# untitled.net
KiCad netlist of a schematic drawn in EAGLE
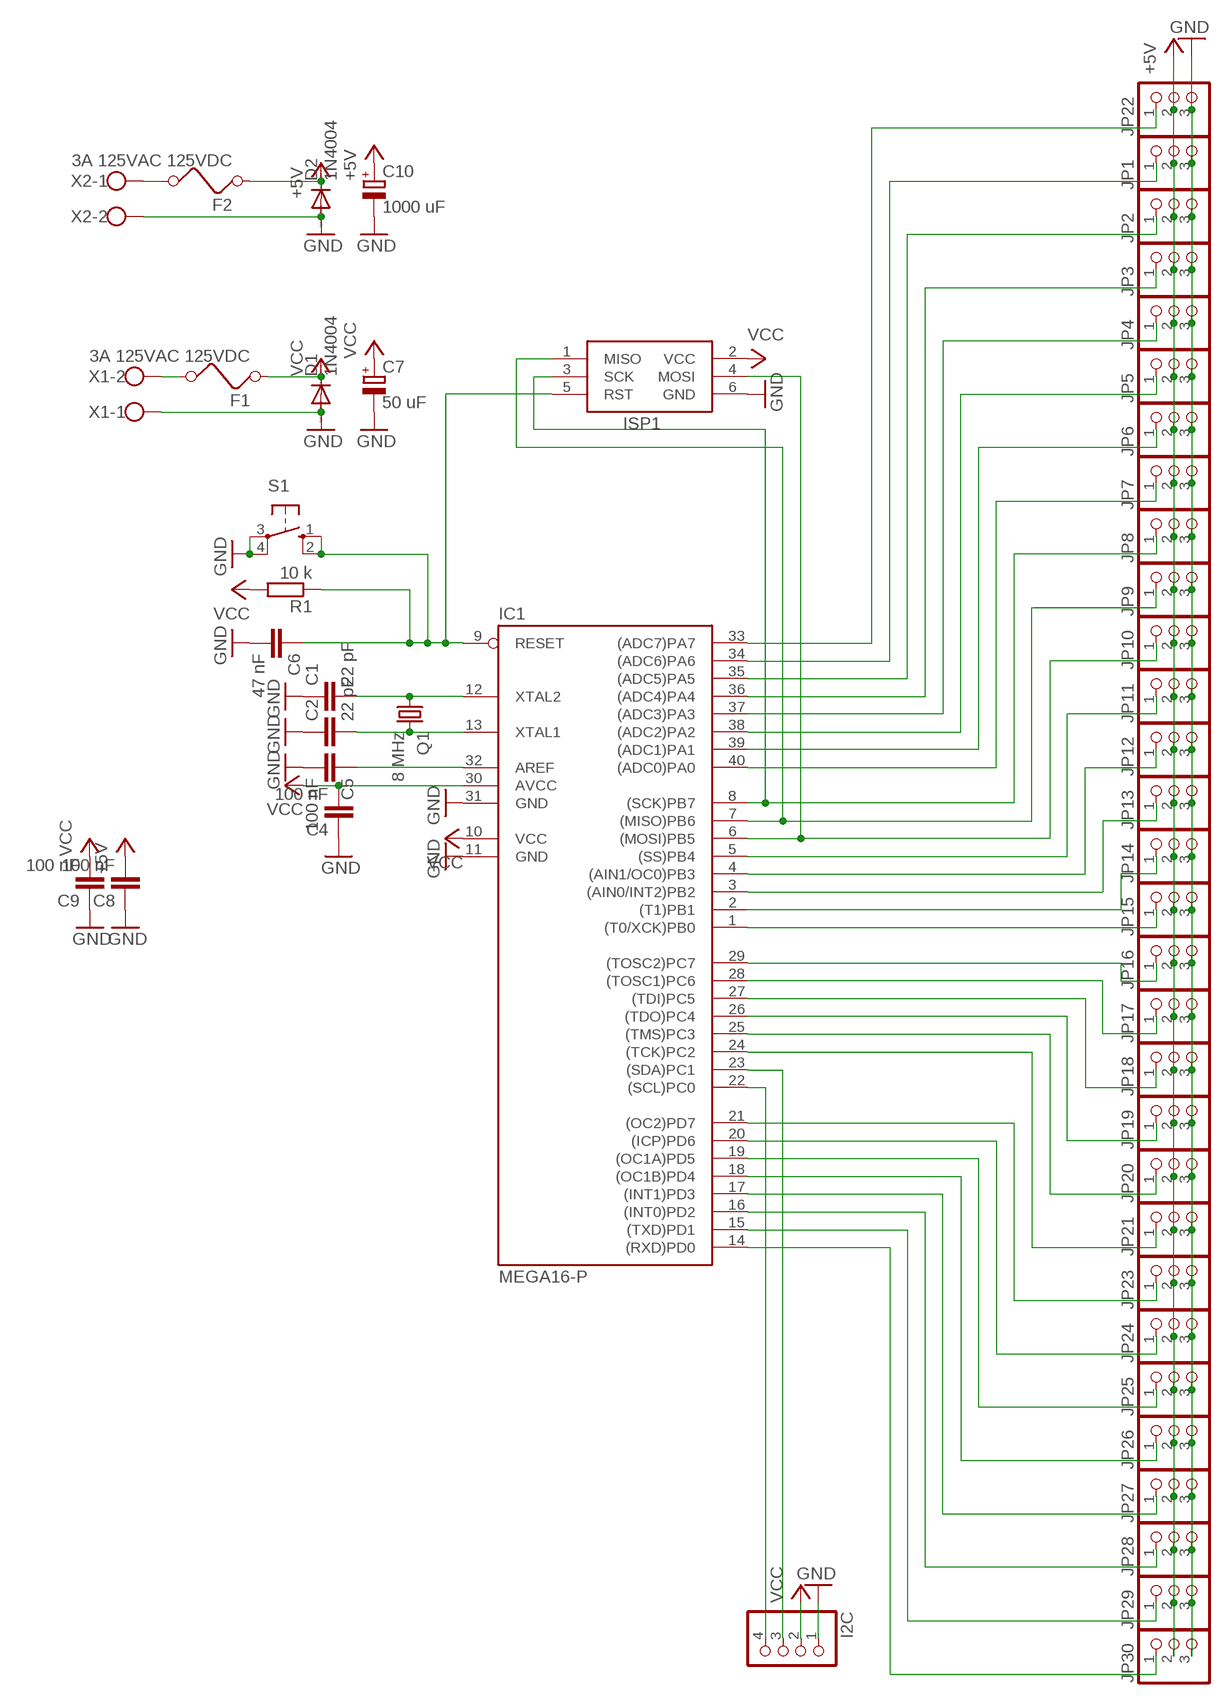
[diagram p0: schematic, sheet 1]

(export (version "E")
  (design (tool "Eeschema 10.0.6"))
  (components
    (comp (ref "C1")
      (value "22 pF")
      (footprint "eagle-import:C0805")
      (libsource (lib "eagle-import") (part "C-EUC0805"))
    )
    (comp (ref "C2")
      (value "22 pF")
      (footprint "eagle-import:C0805")
      (libsource (lib "eagle-import") (part "C-EUC0805"))
    )
    (comp (ref "C4")
      (value "100 nF")
      (footprint "eagle-import:C0805")
      (libsource (lib "eagle-import") (part "C-EUC0805"))
    )
    (comp (ref "C5")
      (value "100 nF")
      (footprint "eagle-import:C0805")
      (libsource (lib "eagle-import") (part "C-EUC0805"))
    )
    (comp (ref "C6")
      (value "47 nF")
      (footprint "eagle-import:C0805")
      (libsource (lib "eagle-import") (part "C-EUC0805"))
    )
    (comp (ref "C7")
      (value "50 uF")
      (footprint "eagle-import:E2-5")
      (libsource (lib "eagle-import") (part "CPOL-EUE2-5"))
    )
    (comp (ref "C8")
      (value "100 nF")
      (footprint "eagle-import:C0805")
      (libsource (lib "eagle-import") (part "C-EUC0805"))
    )
    (comp (ref "C9")
      (value "100 nF")
      (footprint "eagle-import:C0805")
      (libsource (lib "eagle-import") (part "C-EUC0805"))
    )
    (comp (ref "C10")
      (value "1000 uF")
      (footprint "eagle-import:E2-5")
      (libsource (lib "eagle-import") (part "CPOL-EUE2-5"))
    )
    (comp (ref "D1")
      (value "1N4004")
      (footprint "eagle-import:DO214AC")
      (libsource (lib "eagle-import") (part "DIODE-DO214AC"))
    )
    (comp (ref "D2")
      (value "1N4004")
      (footprint "eagle-import:DO214AC")
      (libsource (lib "eagle-import") (part "DIODE-DO214AC"))
    )
    (comp (ref "F1")
      (value "3A 125VAC 125VDC")
      (footprint "eagle-import:FUSE")
      (libsource (lib "eagle-import") (part "FUSE"))
    )
    (comp (ref "F2")
      (value "3A 125VAC 125VDC")
      (footprint "eagle-import:FUSE")
      (libsource (lib "eagle-import") (part "FUSE"))
    )
    (comp (ref "I2C")
      (value "PINHD-1X4")
      (footprint "eagle-import:1X04")
      (libsource (lib "eagle-import") (part "PINHD-1X4"))
    )
    (comp (ref "IC1")
      (value "MEGA16-P")
      (footprint "eagle-import:DIL40")
      (fields (field (name "MPN") "ATMEGA16-16PU"))
      (libsource (lib "eagle-import") (part "MEGA16-P"))
    )
    (comp (ref "ISP1")
      (value "AVRISP-6")
      (footprint "eagle-import:AVRISP")
      (libsource (lib "eagle-import") (part "AVRISP-6"))
    )
    (comp (ref "JP1")
      (value "PINHD-1X3")
      (footprint "eagle-import:1X03")
      (libsource (lib "eagle-import") (part "PINHD-1X3"))
    )
    (comp (ref "JP2")
      (value "PINHD-1X3")
      (footprint "eagle-import:1X03")
      (libsource (lib "eagle-import") (part "PINHD-1X3"))
    )
    (comp (ref "JP3")
      (value "PINHD-1X3")
      (footprint "eagle-import:1X03")
      (libsource (lib "eagle-import") (part "PINHD-1X3"))
    )
    (comp (ref "JP4")
      (value "PINHD-1X3")
      (footprint "eagle-import:1X03")
      (libsource (lib "eagle-import") (part "PINHD-1X3"))
    )
    (comp (ref "JP5")
      (value "PINHD-1X3")
      (footprint "eagle-import:1X03")
      (libsource (lib "eagle-import") (part "PINHD-1X3"))
    )
    (comp (ref "JP6")
      (value "PINHD-1X3")
      (footprint "eagle-import:1X03")
      (libsource (lib "eagle-import") (part "PINHD-1X3"))
    )
    (comp (ref "JP7")
      (value "PINHD-1X3")
      (footprint "eagle-import:1X03")
      (libsource (lib "eagle-import") (part "PINHD-1X3"))
    )
    (comp (ref "JP8")
      (value "PINHD-1X3")
      (footprint "eagle-import:1X03")
      (libsource (lib "eagle-import") (part "PINHD-1X3"))
    )
    (comp (ref "JP9")
      (value "PINHD-1X3")
      (footprint "eagle-import:1X03")
      (libsource (lib "eagle-import") (part "PINHD-1X3"))
    )
    (comp (ref "JP10")
      (value "PINHD-1X3")
      (footprint "eagle-import:1X03")
      (libsource (lib "eagle-import") (part "PINHD-1X3"))
    )
    (comp (ref "JP11")
      (value "PINHD-1X3")
      (footprint "eagle-import:1X03")
      (libsource (lib "eagle-import") (part "PINHD-1X3"))
    )
    (comp (ref "JP12")
      (value "PINHD-1X3")
      (footprint "eagle-import:1X03")
      (libsource (lib "eagle-import") (part "PINHD-1X3"))
    )
    (comp (ref "JP13")
      (value "PINHD-1X3")
      (footprint "eagle-import:1X03")
      (libsource (lib "eagle-import") (part "PINHD-1X3"))
    )
    (comp (ref "JP14")
      (value "PINHD-1X3")
      (footprint "eagle-import:1X03")
      (libsource (lib "eagle-import") (part "PINHD-1X3"))
    )
    (comp (ref "JP15")
      (value "PINHD-1X3")
      (footprint "eagle-import:1X03")
      (libsource (lib "eagle-import") (part "PINHD-1X3"))
    )
    (comp (ref "JP16")
      (value "PINHD-1X3")
      (footprint "eagle-import:1X03")
      (libsource (lib "eagle-import") (part "PINHD-1X3"))
    )
    (comp (ref "JP17")
      (value "PINHD-1X3")
      (footprint "eagle-import:1X03")
      (libsource (lib "eagle-import") (part "PINHD-1X3"))
    )
    (comp (ref "JP18")
      (value "PINHD-1X3")
      (footprint "eagle-import:1X03")
      (libsource (lib "eagle-import") (part "PINHD-1X3"))
    )
    (comp (ref "JP19")
      (value "PINHD-1X3")
      (footprint "eagle-import:1X03")
      (libsource (lib "eagle-import") (part "PINHD-1X3"))
    )
    (comp (ref "JP20")
      (value "PINHD-1X3")
      (footprint "eagle-import:1X03")
      (libsource (lib "eagle-import") (part "PINHD-1X3"))
    )
    (comp (ref "JP21")
      (value "PINHD-1X3")
      (footprint "eagle-import:1X03")
      (libsource (lib "eagle-import") (part "PINHD-1X3"))
    )
    (comp (ref "JP22")
      (value "PINHD-1X3")
      (footprint "eagle-import:1X03")
      (libsource (lib "eagle-import") (part "PINHD-1X3"))
    )
    (comp (ref "JP23")
      (value "PINHD-1X3")
      (footprint "eagle-import:1X03")
      (libsource (lib "eagle-import") (part "PINHD-1X3"))
    )
    (comp (ref "JP24")
      (value "PINHD-1X3")
      (footprint "eagle-import:1X03")
      (libsource (lib "eagle-import") (part "PINHD-1X3"))
    )
    (comp (ref "JP25")
      (value "PINHD-1X3")
      (footprint "eagle-import:1X03")
      (libsource (lib "eagle-import") (part "PINHD-1X3"))
    )
    (comp (ref "JP26")
      (value "PINHD-1X3")
      (footprint "eagle-import:1X03")
      (libsource (lib "eagle-import") (part "PINHD-1X3"))
    )
    (comp (ref "JP27")
      (value "PINHD-1X3")
      (footprint "eagle-import:1X03")
      (libsource (lib "eagle-import") (part "PINHD-1X3"))
    )
    (comp (ref "JP28")
      (value "PINHD-1X3")
      (footprint "eagle-import:1X03")
      (libsource (lib "eagle-import") (part "PINHD-1X3"))
    )
    (comp (ref "JP29")
      (value "PINHD-1X3")
      (footprint "eagle-import:1X03")
      (libsource (lib "eagle-import") (part "PINHD-1X3"))
    )
    (comp (ref "JP30")
      (value "PINHD-1X3")
      (footprint "eagle-import:1X03")
      (libsource (lib "eagle-import") (part "PINHD-1X3"))
    )
    (comp (ref "Q1")
      (value "8 MHz")
      (footprint "eagle-import:HC49_S")
      (libsource (lib "eagle-import") (part "CRYSTALHC49S"))
    )
    (comp (ref "R1")
      (value "10 k")
      (footprint "eagle-import:R0805")
      (libsource (lib "eagle-import") (part "R-EU_R0805"))
    )
    (comp (ref "S1")
      (value "10-XX")
      (footprint "eagle-import:B3F-10XX")
      (fields (field (name "MPN") "B3F-1000"))
      (libsource (lib "eagle-import") (part "10-XX"))
    )
    (comp (ref "X1")
      (value "W237-102")
      (footprint "eagle-import:W237-102")
      (fields (field (name "MPN") "237-102"))
      (libsource (lib "eagle-import") (part "W237-102"))
    )
    (comp (ref "X2")
      (value "W237-102")
      (footprint "eagle-import:W237-102")
      (fields (field (name "MPN") "237-102"))
      (libsource (lib "eagle-import") (part "W237-102"))
    )
  )
  (nets
    (net (code "1") (name "+5V") (class "Default")
      (node (ref "C10") (pin "+") (pinfunction "+_+") (pintype "passive"))
      (node (ref "C8") (pin "2") (pinfunction "2_2") (pintype "passive"))
      (node (ref "D2") (pin "C") (pinfunction "C_C") (pintype "passive"))
      (node (ref "F2") (pin "1") (pinfunction "1_1") (pintype "passive"))
      (node (ref "JP1") (pin "2") (pinfunction "2_2") (pintype "passive"))
      (node (ref "JP10") (pin "2") (pinfunction "2_2") (pintype "passive"))
      (node (ref "JP11") (pin "2") (pinfunction "2_2") (pintype "passive"))
      (node (ref "JP12") (pin "2") (pinfunction "2_2") (pintype "passive"))
      (node (ref "JP13") (pin "2") (pinfunction "2_2") (pintype "passive"))
      (node (ref "JP14") (pin "2") (pinfunction "2_2") (pintype "passive"))
      (node (ref "JP15") (pin "2") (pinfunction "2_2") (pintype "passive"))
      (node (ref "JP16") (pin "2") (pinfunction "2_2") (pintype "passive"))
      (node (ref "JP17") (pin "2") (pinfunction "2_2") (pintype "passive"))
      (node (ref "JP18") (pin "2") (pinfunction "2_2") (pintype "passive"))
      (node (ref "JP19") (pin "2") (pinfunction "2_2") (pintype "passive"))
      (node (ref "JP2") (pin "2") (pinfunction "2_2") (pintype "passive"))
      (node (ref "JP20") (pin "2") (pinfunction "2_2") (pintype "passive"))
      (node (ref "JP21") (pin "2") (pinfunction "2_2") (pintype "passive"))
      (node (ref "JP22") (pin "2") (pinfunction "2_2") (pintype "passive"))
      (node (ref "JP23") (pin "2") (pinfunction "2_2") (pintype "passive"))
      (node (ref "JP24") (pin "2") (pinfunction "2_2") (pintype "passive"))
      (node (ref "JP25") (pin "2") (pinfunction "2_2") (pintype "passive"))
      (node (ref "JP26") (pin "2") (pinfunction "2_2") (pintype "passive"))
      (node (ref "JP27") (pin "2") (pinfunction "2_2") (pintype "passive"))
      (node (ref "JP28") (pin "2") (pinfunction "2_2") (pintype "passive"))
      (node (ref "JP29") (pin "2") (pinfunction "2_2") (pintype "passive"))
      (node (ref "JP3") (pin "2") (pinfunction "2_2") (pintype "passive"))
      (node (ref "JP30") (pin "2") (pinfunction "2_2") (pintype "passive"))
      (node (ref "JP4") (pin "2") (pinfunction "2_2") (pintype "passive"))
      (node (ref "JP5") (pin "2") (pinfunction "2_2") (pintype "passive"))
      (node (ref "JP6") (pin "2") (pinfunction "2_2") (pintype "passive"))
      (node (ref "JP7") (pin "2") (pinfunction "2_2") (pintype "passive"))
      (node (ref "JP8") (pin "2") (pinfunction "2_2") (pintype "passive"))
      (node (ref "JP9") (pin "2") (pinfunction "2_2") (pintype "passive"))
    )
    (net (code "2") (name "GND") (class "Default")
      (node (ref "C1") (pin "1") (pinfunction "1_1") (pintype "passive"))
      (node (ref "C10") (pin "-") (pinfunction "-_-") (pintype "passive"))
      (node (ref "C2") (pin "1") (pinfunction "1_1") (pintype "passive"))
      (node (ref "C4") (pin "1") (pinfunction "1_1") (pintype "passive"))
      (node (ref "C5") (pin "2") (pinfunction "2_2") (pintype "passive"))
      (node (ref "C6") (pin "2") (pinfunction "2_2") (pintype "passive"))
      (node (ref "C7") (pin "-") (pinfunction "-_-") (pintype "passive"))
      (node (ref "C8") (pin "1") (pinfunction "1_1") (pintype "passive"))
      (node (ref "C9") (pin "1") (pinfunction "1_1") (pintype "passive"))
      (node (ref "D1") (pin "A") (pinfunction "A_A") (pintype "passive"))
      (node (ref "D2") (pin "A") (pinfunction "A_A") (pintype "passive"))
      (node (ref "I2C") (pin "1") (pinfunction "1_1") (pintype "passive"))
      (node (ref "IC1") (pin "11") (pinfunction "GND_11") (pintype "power_in"))
      (node (ref "IC1") (pin "31") (pinfunction "GND_31") (pintype "power_in"))
      (node (ref "ISP1") (pin "6") (pinfunction "GND_6") (pintype "power_in"))
      (node (ref "JP1") (pin "3") (pinfunction "3_3") (pintype "passive"))
      (node (ref "JP10") (pin "3") (pinfunction "3_3") (pintype "passive"))
      (node (ref "JP11") (pin "3") (pinfunction "3_3") (pintype "passive"))
      (node (ref "JP12") (pin "3") (pinfunction "3_3") (pintype "passive"))
      (node (ref "JP13") (pin "3") (pinfunction "3_3") (pintype "passive"))
      (node (ref "JP14") (pin "3") (pinfunction "3_3") (pintype "passive"))
      (node (ref "JP15") (pin "3") (pinfunction "3_3") (pintype "passive"))
      (node (ref "JP16") (pin "3") (pinfunction "3_3") (pintype "passive"))
      (node (ref "JP17") (pin "3") (pinfunction "3_3") (pintype "passive"))
      (node (ref "JP18") (pin "3") (pinfunction "3_3") (pintype "passive"))
      (node (ref "JP19") (pin "3") (pinfunction "3_3") (pintype "passive"))
      (node (ref "JP2") (pin "3") (pinfunction "3_3") (pintype "passive"))
      (node (ref "JP20") (pin "3") (pinfunction "3_3") (pintype "passive"))
      (node (ref "JP21") (pin "3") (pinfunction "3_3") (pintype "passive"))
      (node (ref "JP22") (pin "3") (pinfunction "3_3") (pintype "passive"))
      (node (ref "JP23") (pin "3") (pinfunction "3_3") (pintype "passive"))
      (node (ref "JP24") (pin "3") (pinfunction "3_3") (pintype "passive"))
      (node (ref "JP25") (pin "3") (pinfunction "3_3") (pintype "passive"))
      (node (ref "JP26") (pin "3") (pinfunction "3_3") (pintype "passive"))
      (node (ref "JP27") (pin "3") (pinfunction "3_3") (pintype "passive"))
      (node (ref "JP28") (pin "3") (pinfunction "3_3") (pintype "passive"))
      (node (ref "JP29") (pin "3") (pinfunction "3_3") (pintype "passive"))
      (node (ref "JP3") (pin "3") (pinfunction "3_3") (pintype "passive"))
      (node (ref "JP30") (pin "3") (pinfunction "3_3") (pintype "passive"))
      (node (ref "JP4") (pin "3") (pinfunction "3_3") (pintype "passive"))
      (node (ref "JP5") (pin "3") (pinfunction "3_3") (pintype "passive"))
      (node (ref "JP6") (pin "3") (pinfunction "3_3") (pintype "passive"))
      (node (ref "JP7") (pin "3") (pinfunction "3_3") (pintype "passive"))
      (node (ref "JP8") (pin "3") (pinfunction "3_3") (pintype "passive"))
      (node (ref "JP9") (pin "3") (pinfunction "3_3") (pintype "passive"))
      (node (ref "S1") (pin "3") (pinfunction "P_3") (pintype "passive"))
      (node (ref "S1") (pin "4") (pinfunction "P1_4") (pintype "passive"))
      (node (ref "X1") (pin "1") (pinfunction "KL_1") (pintype "passive"))
      (node (ref "X2") (pin "2") (pinfunction "KL_2") (pintype "passive"))
    )
    (net (code "3") (name "Net-(IC1-(ADC0)PA0)") (class "Default")
      (node (ref "IC1") (pin "40") (pinfunction "(ADC0)PA0_40") (pintype "bidirectional"))
      (node (ref "JP7") (pin "1") (pinfunction "1_1") (pintype "passive"))
    )
    (net (code "4") (name "Net-(IC1-(ADC1)PA1)") (class "Default")
      (node (ref "IC1") (pin "39") (pinfunction "(ADC1)PA1_39") (pintype "bidirectional"))
      (node (ref "JP6") (pin "1") (pinfunction "1_1") (pintype "passive"))
    )
    (net (code "5") (name "Net-(IC1-(ADC2)PA2)") (class "Default")
      (node (ref "IC1") (pin "38") (pinfunction "(ADC2)PA2_38") (pintype "bidirectional"))
      (node (ref "JP5") (pin "1") (pinfunction "1_1") (pintype "passive"))
    )
    (net (code "6") (name "Net-(IC1-(ADC3)PA3)") (class "Default")
      (node (ref "IC1") (pin "37") (pinfunction "(ADC3)PA3_37") (pintype "bidirectional"))
      (node (ref "JP4") (pin "1") (pinfunction "1_1") (pintype "passive"))
    )
    (net (code "7") (name "Net-(IC1-(ADC4)PA4)") (class "Default")
      (node (ref "IC1") (pin "36") (pinfunction "(ADC4)PA4_36") (pintype "bidirectional"))
      (node (ref "JP3") (pin "1") (pinfunction "1_1") (pintype "passive"))
    )
    (net (code "8") (name "Net-(IC1-(ADC5)PA5)") (class "Default")
      (node (ref "IC1") (pin "35") (pinfunction "(ADC5)PA5_35") (pintype "bidirectional"))
      (node (ref "JP2") (pin "1") (pinfunction "1_1") (pintype "passive"))
    )
    (net (code "9") (name "Net-(IC1-(ADC6)PA6)") (class "Default")
      (node (ref "IC1") (pin "34") (pinfunction "(ADC6)PA6_34") (pintype "bidirectional"))
      (node (ref "JP1") (pin "1") (pinfunction "1_1") (pintype "passive"))
    )
    (net (code "10") (name "Net-(IC1-(ADC7)PA7)") (class "Default")
      (node (ref "IC1") (pin "33") (pinfunction "(ADC7)PA7_33") (pintype "bidirectional"))
      (node (ref "JP22") (pin "1") (pinfunction "1_1") (pintype "passive"))
    )
    (net (code "11") (name "Net-(IC1-(AIN0{slash}INT2)PB2)") (class "Default")
      (node (ref "IC1") (pin "3") (pinfunction "(AIN0/INT2)PB2_3") (pintype "bidirectional"))
      (node (ref "JP13") (pin "1") (pinfunction "1_1") (pintype "passive"))
    )
    (net (code "12") (name "Net-(IC1-(AIN1{slash}OC0)PB3)") (class "Default")
      (node (ref "IC1") (pin "4") (pinfunction "(AIN1/OC0)PB3_4") (pintype "bidirectional"))
      (node (ref "JP12") (pin "1") (pinfunction "1_1") (pintype "passive"))
    )
    (net (code "13") (name "Net-(IC1-(ICP)PD6)") (class "Default")
      (node (ref "IC1") (pin "20") (pinfunction "(ICP)PD6_20") (pintype "bidirectional"))
      (node (ref "JP24") (pin "1") (pinfunction "1_1") (pintype "passive"))
    )
    (net (code "14") (name "Net-(IC1-(INT0)PD2)") (class "Default")
      (node (ref "IC1") (pin "16") (pinfunction "(INT0)PD2_16") (pintype "bidirectional"))
      (node (ref "JP28") (pin "1") (pinfunction "1_1") (pintype "passive"))
    )
    (net (code "15") (name "Net-(IC1-(INT1)PD3)") (class "Default")
      (node (ref "IC1") (pin "17") (pinfunction "(INT1)PD3_17") (pintype "bidirectional"))
      (node (ref "JP27") (pin "1") (pinfunction "1_1") (pintype "passive"))
    )
    (net (code "16") (name "Net-(IC1-(MISO)PB6)") (class "Default")
      (node (ref "IC1") (pin "7") (pinfunction "(MISO)PB6_7") (pintype "bidirectional"))
      (node (ref "ISP1") (pin "1") (pinfunction "MISO_1") (pintype "input"))
      (node (ref "JP9") (pin "1") (pinfunction "1_1") (pintype "passive"))
    )
    (net (code "17") (name "Net-(IC1-(MOSI)PB5)") (class "Default")
      (node (ref "IC1") (pin "6") (pinfunction "(MOSI)PB5_6") (pintype "bidirectional"))
      (node (ref "ISP1") (pin "4") (pinfunction "MOSI_4") (pintype "output"))
      (node (ref "JP10") (pin "1") (pinfunction "1_1") (pintype "passive"))
    )
    (net (code "18") (name "Net-(IC1-(OC1A)PD5)") (class "Default")
      (node (ref "IC1") (pin "19") (pinfunction "(OC1A)PD5_19") (pintype "bidirectional"))
      (node (ref "JP25") (pin "1") (pinfunction "1_1") (pintype "passive"))
    )
    (net (code "19") (name "Net-(IC1-(OC1B)PD4)") (class "Default")
      (node (ref "IC1") (pin "18") (pinfunction "(OC1B)PD4_18") (pintype "bidirectional"))
      (node (ref "JP26") (pin "1") (pinfunction "1_1") (pintype "passive"))
    )
    (net (code "20") (name "Net-(IC1-(OC2)PD7)") (class "Default")
      (node (ref "IC1") (pin "21") (pinfunction "(OC2)PD7_21") (pintype "bidirectional"))
      (node (ref "JP23") (pin "1") (pinfunction "1_1") (pintype "passive"))
    )
    (net (code "21") (name "Net-(IC1-(RXD)PD0)") (class "Default")
      (node (ref "IC1") (pin "14") (pinfunction "(RXD)PD0_14") (pintype "bidirectional"))
      (node (ref "JP30") (pin "1") (pinfunction "1_1") (pintype "passive"))
    )
    (net (code "22") (name "Net-(IC1-(SCK)PB7)") (class "Default")
      (node (ref "IC1") (pin "8") (pinfunction "(SCK)PB7_8") (pintype "bidirectional"))
      (node (ref "ISP1") (pin "3") (pinfunction "SCK_3") (pintype "output"))
      (node (ref "JP8") (pin "1") (pinfunction "1_1") (pintype "passive"))
    )
    (net (code "23") (name "Net-(IC1-(SCL)PC0)") (class "Default")
      (node (ref "I2C") (pin "4") (pinfunction "4_4") (pintype "passive"))
      (node (ref "IC1") (pin "22") (pinfunction "(SCL)PC0_22") (pintype "bidirectional"))
    )
    (net (code "24") (name "Net-(IC1-(SDA)PC1)") (class "Default")
      (node (ref "I2C") (pin "3") (pinfunction "3_3") (pintype "passive"))
      (node (ref "IC1") (pin "23") (pinfunction "(SDA)PC1_23") (pintype "bidirectional"))
    )
    (net (code "25") (name "Net-(IC1-(SS)PB4)") (class "Default")
      (node (ref "IC1") (pin "5") (pinfunction "(SS)PB4_5") (pintype "bidirectional"))
      (node (ref "JP11") (pin "1") (pinfunction "1_1") (pintype "passive"))
    )
    (net (code "26") (name "Net-(IC1-(T0{slash}XCK)PB0)") (class "Default")
      (node (ref "IC1") (pin "1") (pinfunction "(T0/XCK)PB0_1") (pintype "bidirectional"))
      (node (ref "JP15") (pin "1") (pinfunction "1_1") (pintype "passive"))
    )
    (net (code "27") (name "Net-(IC1-(T1)PB1)") (class "Default")
      (node (ref "IC1") (pin "2") (pinfunction "(T1)PB1_2") (pintype "bidirectional"))
      (node (ref "JP14") (pin "1") (pinfunction "1_1") (pintype "passive"))
    )
    (net (code "28") (name "Net-(IC1-(TCK)PC2)") (class "Default")
      (node (ref "IC1") (pin "24") (pinfunction "(TCK)PC2_24") (pintype "bidirectional"))
      (node (ref "JP21") (pin "1") (pinfunction "1_1") (pintype "passive"))
    )
    (net (code "29") (name "Net-(IC1-(TDI)PC5)") (class "Default")
      (node (ref "IC1") (pin "27") (pinfunction "(TDI)PC5_27") (pintype "bidirectional"))
      (node (ref "JP18") (pin "1") (pinfunction "1_1") (pintype "passive"))
    )
    (net (code "30") (name "Net-(IC1-(TDO)PC4)") (class "Default")
      (node (ref "IC1") (pin "26") (pinfunction "(TDO)PC4_26") (pintype "bidirectional"))
      (node (ref "JP19") (pin "1") (pinfunction "1_1") (pintype "passive"))
    )
    (net (code "31") (name "Net-(IC1-(TMS)PC3)") (class "Default")
      (node (ref "IC1") (pin "25") (pinfunction "(TMS)PC3_25") (pintype "bidirectional"))
      (node (ref "JP20") (pin "1") (pinfunction "1_1") (pintype "passive"))
    )
    (net (code "32") (name "Net-(IC1-(TOSC1)PC6)") (class "Default")
      (node (ref "IC1") (pin "28") (pinfunction "(TOSC1)PC6_28") (pintype "bidirectional"))
      (node (ref "JP17") (pin "1") (pinfunction "1_1") (pintype "passive"))
    )
    (net (code "33") (name "Net-(IC1-(TOSC2)PC7)") (class "Default")
      (node (ref "IC1") (pin "29") (pinfunction "(TOSC2)PC7_29") (pintype "bidirectional"))
      (node (ref "JP16") (pin "1") (pinfunction "1_1") (pintype "passive"))
    )
    (net (code "34") (name "Net-(IC1-(TXD)PD1)") (class "Default")
      (node (ref "IC1") (pin "15") (pinfunction "(TXD)PD1_15") (pintype "bidirectional"))
      (node (ref "JP29") (pin "1") (pinfunction "1_1") (pintype "passive"))
    )
    (net (code "35") (name "Net-(IC1-AREF)") (class "Default")
      (node (ref "C5") (pin "1") (pinfunction "1_1") (pintype "passive"))
      (node (ref "IC1") (pin "32") (pinfunction "AREF_32") (pintype "passive"))
    )
    (net (code "36") (name "Net-(IC1-RESET)") (class "Default")
      (node (ref "C6") (pin "1") (pinfunction "1_1") (pintype "passive"))
      (node (ref "IC1") (pin "9") (pinfunction "RESET_9") (pintype "input"))
      (node (ref "ISP1") (pin "5") (pinfunction "RST_5") (pintype "output"))
      (node (ref "R1") (pin "1") (pinfunction "1_1") (pintype "passive"))
      (node (ref "S1") (pin "1") (pinfunction "S_1") (pintype "passive"))
      (node (ref "S1") (pin "2") (pinfunction "S1_2") (pintype "passive"))
    )
    (net (code "37") (name "Net-(IC1-XTAL1)") (class "Default")
      (node (ref "C2") (pin "2") (pinfunction "2_2") (pintype "passive"))
      (node (ref "IC1") (pin "13") (pinfunction "XTAL1_13") (pintype "bidirectional"))
      (node (ref "Q1") (pin "2") (pinfunction "2_2") (pintype "passive"))
    )
    (net (code "38") (name "Net-(IC1-XTAL2)") (class "Default")
      (node (ref "C1") (pin "2") (pinfunction "2_2") (pintype "passive"))
      (node (ref "IC1") (pin "12") (pinfunction "XTAL2_12") (pintype "bidirectional"))
      (node (ref "Q1") (pin "1") (pinfunction "1_1") (pintype "passive"))
    )
    (net (code "39") (name "Net-(X1B-KL)") (class "Default")
      (node (ref "F1") (pin "2") (pinfunction "2_2") (pintype "passive"))
      (node (ref "X1") (pin "2") (pinfunction "KL_2") (pintype "passive"))
    )
    (net (code "40") (name "Net-(X2A-KL)") (class "Default")
      (node (ref "F2") (pin "2") (pinfunction "2_2") (pintype "passive"))
      (node (ref "X2") (pin "1") (pinfunction "KL_1") (pintype "passive"))
    )
    (net (code "41") (name "VCC") (class "Default")
      (node (ref "C4") (pin "2") (pinfunction "2_2") (pintype "passive"))
      (node (ref "C7") (pin "+") (pinfunction "+_+") (pintype "passive"))
      (node (ref "C9") (pin "2") (pinfunction "2_2") (pintype "passive"))
      (node (ref "D1") (pin "C") (pinfunction "C_C") (pintype "passive"))
      (node (ref "F1") (pin "1") (pinfunction "1_1") (pintype "passive"))
      (node (ref "I2C") (pin "2") (pinfunction "2_2") (pintype "passive"))
      (node (ref "IC1") (pin "10") (pinfunction "VCC_10") (pintype "power_in"))
      (node (ref "IC1") (pin "30") (pinfunction "AVCC_30") (pintype "power_in"))
      (node (ref "ISP1") (pin "2") (pinfunction "VCC_2") (pintype "power_in"))
      (node (ref "R1") (pin "2") (pinfunction "2_2") (pintype "passive"))
    )
  )
)
